# DAU_Kupplung_3phasig_V1_10.net
KiCad netlist of a schematic drawn in EAGLE
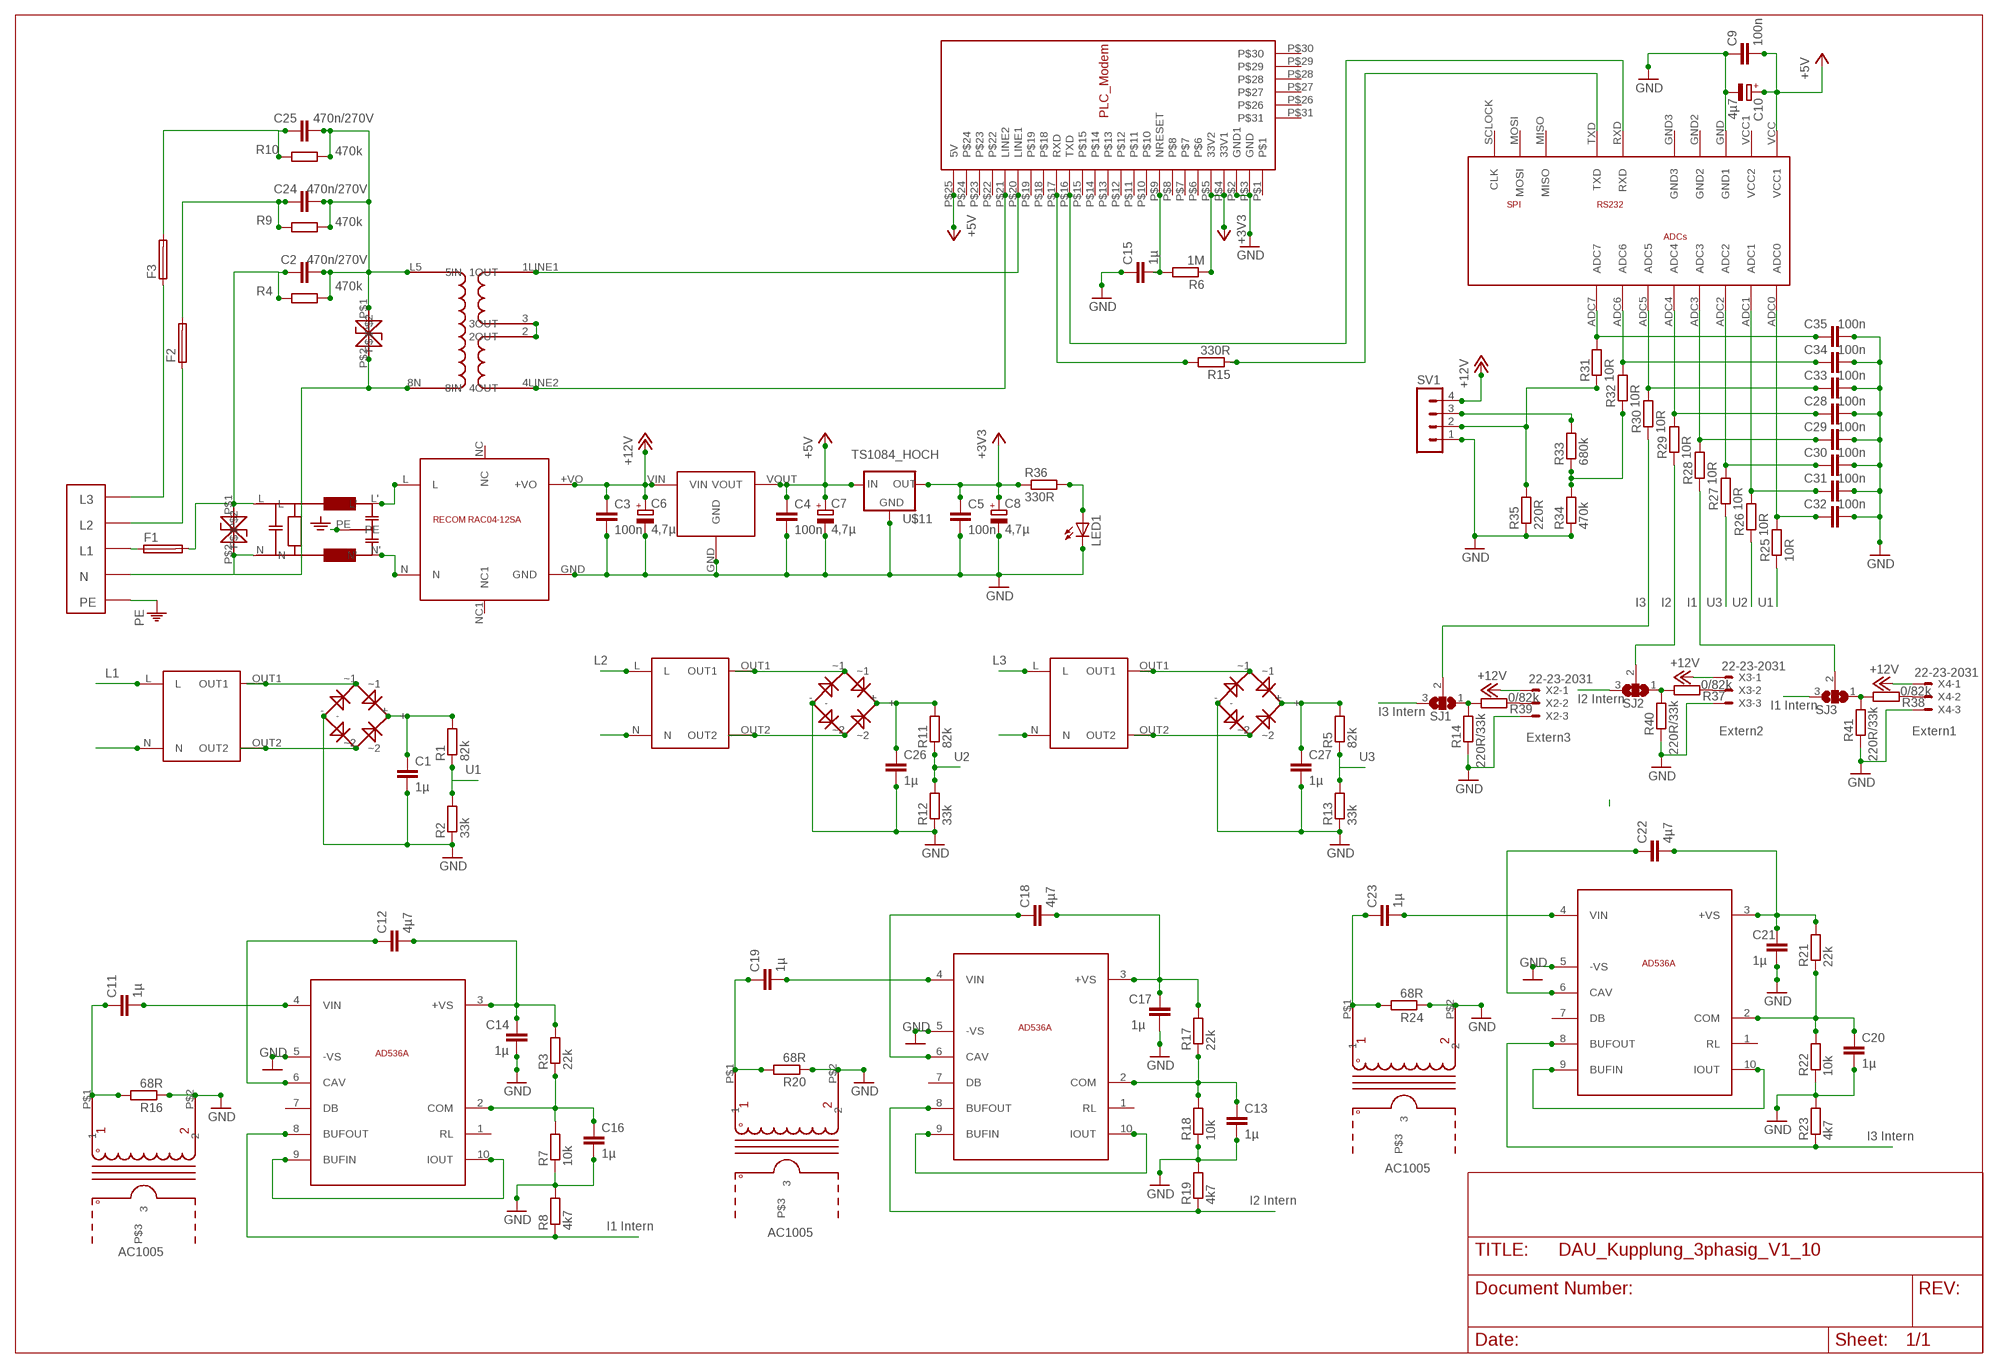
[diagram p0: schematic, sheet 1]

(export (version "E")
  (design (tool "Eeschema 10.0.6"))
  (components
    (comp (ref "AC1002_1")
      (value "AC1010")
      (footprint "eagle-import:AC1010")
      (libsource (lib "eagle-import") (part "AC1010"))
    )
    (comp (ref "C1")
      (value "1µ")
      (footprint "eagle-import:C0805K")
      (libsource (lib "eagle-import") (part "C-EUC0805K"))
    )
    (comp (ref "C2")
      (value "470n/270V")
      (footprint "eagle-import:C225-087X268")
      (libsource (lib "eagle-import") (part "C-EU225-087X268"))
    )
    (comp (ref "C3")
      (value "100n")
      (footprint "eagle-import:C0805K")
      (libsource (lib "eagle-import") (part "C-EUC0805K"))
    )
    (comp (ref "C4")
      (value "100n")
      (footprint "eagle-import:C0805K")
      (libsource (lib "eagle-import") (part "C-EUC0805K"))
    )
    (comp (ref "C5")
      (value "100n")
      (footprint "eagle-import:C0805K")
      (libsource (lib "eagle-import") (part "C-EUC0805K"))
    )
    (comp (ref "C6")
      (value "4,7µ")
      (footprint "eagle-import:E2,5-6")
      (libsource (lib "eagle-import") (part "resistor_CPOL-EUE2.5-6"))
    )
    (comp (ref "C7")
      (value "4,7µ")
      (footprint "eagle-import:E2,5-6")
      (libsource (lib "eagle-import") (part "resistor_CPOL-EUE2.5-6"))
    )
    (comp (ref "C8")
      (value "4,7µ")
      (footprint "eagle-import:E2,5-6")
      (libsource (lib "eagle-import") (part "resistor_CPOL-EUE2.5-6"))
    )
    (comp (ref "C9")
      (value "100n")
      (footprint "eagle-import:C0805K")
      (libsource (lib "eagle-import") (part "C-EUC0805K"))
    )
    (comp (ref "C10")
      (value "4µ7")
      (footprint "eagle-import:E2,5-6E")
      (libsource (lib "eagle-import") (part "CPOL-EUE2,5-6E"))
    )
    (comp (ref "C11")
      (value "1µ")
      (footprint "eagle-import:C0805K")
      (libsource (lib "eagle-import") (part "C-EUC0805K"))
    )
    (comp (ref "C12")
      (value "4µ7")
      (footprint "eagle-import:C0805K")
      (libsource (lib "eagle-import") (part "C-EUC0805K"))
    )
    (comp (ref "C13")
      (value "1µ")
      (footprint "eagle-import:C0805K")
      (libsource (lib "eagle-import") (part "C-EUC0805K"))
    )
    (comp (ref "C14")
      (value "1µ")
      (footprint "eagle-import:C0805K")
      (libsource (lib "eagle-import") (part "C-EUC0805K"))
    )
    (comp (ref "C15")
      (value "1µ")
      (footprint "eagle-import:C0805K")
      (libsource (lib "eagle-import") (part "C-EUC0805K"))
    )
    (comp (ref "C16")
      (value "1µ")
      (footprint "eagle-import:C0805K")
      (libsource (lib "eagle-import") (part "C-EUC0805K"))
    )
    (comp (ref "C17")
      (value "1µ")
      (footprint "eagle-import:C0805K")
      (libsource (lib "eagle-import") (part "C-EUC0805K"))
    )
    (comp (ref "C18")
      (value "4µ7")
      (footprint "eagle-import:C0805K")
      (libsource (lib "eagle-import") (part "C-EUC0805K"))
    )
    (comp (ref "C19")
      (value "1µ")
      (footprint "eagle-import:C0805K")
      (libsource (lib "eagle-import") (part "C-EUC0805K"))
    )
    (comp (ref "C20")
      (value "1µ")
      (footprint "eagle-import:C0805K")
      (libsource (lib "eagle-import") (part "C-EUC0805K"))
    )
    (comp (ref "C21")
      (value "1µ")
      (footprint "eagle-import:C0805K")
      (libsource (lib "eagle-import") (part "C-EUC0805K"))
    )
    (comp (ref "C22")
      (value "4µ7")
      (footprint "eagle-import:C0805K")
      (libsource (lib "eagle-import") (part "C-EUC0805K"))
    )
    (comp (ref "C23")
      (value "1µ")
      (footprint "eagle-import:C0805K")
      (libsource (lib "eagle-import") (part "C-EUC0805K"))
    )
    (comp (ref "C24")
      (value "470n/270V")
      (footprint "eagle-import:C225-087X268")
      (libsource (lib "eagle-import") (part "C-EU225-087X268"))
    )
    (comp (ref "C25")
      (value "470n/270V")
      (footprint "eagle-import:C225-087X268")
      (libsource (lib "eagle-import") (part "C-EU225-087X268"))
    )
    (comp (ref "C26")
      (value "1µ")
      (footprint "eagle-import:C0805K")
      (libsource (lib "eagle-import") (part "C-EUC0805K"))
    )
    (comp (ref "C27")
      (value "1µ")
      (footprint "eagle-import:C0805K")
      (libsource (lib "eagle-import") (part "C-EUC0805K"))
    )
    (comp (ref "C28")
      (value "100n")
      (footprint "eagle-import:C0805K")
      (libsource (lib "eagle-import") (part "C-EUC0805K"))
    )
    (comp (ref "C29")
      (value "100n")
      (footprint "eagle-import:C0805K")
      (libsource (lib "eagle-import") (part "C-EUC0805K"))
    )
    (comp (ref "C30")
      (value "100n")
      (footprint "eagle-import:C0805K")
      (libsource (lib "eagle-import") (part "C-EUC0805K"))
    )
    (comp (ref "C31")
      (value "100n")
      (footprint "eagle-import:C0805K")
      (libsource (lib "eagle-import") (part "C-EUC0805K"))
    )
    (comp (ref "C32")
      (value "100n")
      (footprint "eagle-import:C0805K")
      (libsource (lib "eagle-import") (part "C-EUC0805K"))
    )
    (comp (ref "C33")
      (value "100n")
      (footprint "eagle-import:C0805K")
      (libsource (lib "eagle-import") (part "C-EUC0805K"))
    )
    (comp (ref "C34")
      (value "100n")
      (footprint "eagle-import:C0805K")
      (libsource (lib "eagle-import") (part "C-EUC0805K"))
    )
    (comp (ref "C35")
      (value "100n")
      (footprint "eagle-import:C0805K")
      (libsource (lib "eagle-import") (part "C-EUC0805K"))
    )
    (comp (ref "F1")
      (value "TR5")
      (footprint "eagle-import:TR5")
      (libsource (lib "eagle-import") (part "TR5"))
    )
    (comp (ref "F2")
      (value "TR5")
      (footprint "eagle-import:TR5")
      (fields (field (name "OC_FARNELL") "unknown") (field (name "OC_NEWARK") "unknown"))
      (libsource (lib "eagle-import") (part "TR5"))
    )
    (comp (ref "F3")
      (value "TR5")
      (footprint "eagle-import:TR5")
      (fields (field (name "OC_FARNELL") "unknown") (field (name "OC_NEWARK") "unknown"))
      (libsource (lib "eagle-import") (part "TR5"))
    )
    (comp (ref "LED1")
      (value "LEDSQR2X5")
      (footprint "eagle-import:LED2X5")
      (libsource (lib "eagle-import") (part "LEDSQR2X5"))
    )
    (comp (ref "P6KE300CA")
      (value "P6KE300CA")
      (footprint "eagle-import:TSV")
      (libsource (lib "eagle-import") (part "TSV"))
    )
    (comp (ref "R1")
      (value "82k")
      (footprint "eagle-import:R0805")
      (libsource (lib "eagle-import") (part "R-EU_R0805"))
    )
    (comp (ref "R2")
      (value "33k")
      (footprint "eagle-import:R0805")
      (libsource (lib "eagle-import") (part "R-EU_R0805"))
    )
    (comp (ref "R3")
      (value "22k")
      (footprint "eagle-import:R0805")
      (libsource (lib "eagle-import") (part "R-EU_R0805"))
    )
    (comp (ref "R4")
      (value "470k")
      (footprint "eagle-import:0204_7")
      (libsource (lib "eagle-import") (part "R-EU_0204/7"))
    )
    (comp (ref "R5")
      (value "82k")
      (footprint "eagle-import:R0805")
      (libsource (lib "eagle-import") (part "R-EU_R0805"))
    )
    (comp (ref "R6")
      (value "1M")
      (footprint "eagle-import:R0805")
      (libsource (lib "eagle-import") (part "R-EU_R0805"))
    )
    (comp (ref "R7")
      (value "10k")
      (footprint "eagle-import:R0805")
      (libsource (lib "eagle-import") (part "R-EU_R0805"))
    )
    (comp (ref "R8")
      (value "4k7")
      (footprint "eagle-import:R0805")
      (libsource (lib "eagle-import") (part "R-EU_R0805"))
    )
    (comp (ref "R9")
      (value "470k")
      (footprint "eagle-import:0204_7")
      (libsource (lib "eagle-import") (part "R-EU_0204/7"))
    )
    (comp (ref "R10")
      (value "470k")
      (footprint "eagle-import:0204_7")
      (libsource (lib "eagle-import") (part "R-EU_0204/7"))
    )
    (comp (ref "R11")
      (value "82k")
      (footprint "eagle-import:R0805")
      (libsource (lib "eagle-import") (part "R-EU_R0805"))
    )
    (comp (ref "R12")
      (value "33k")
      (footprint "eagle-import:R0805")
      (libsource (lib "eagle-import") (part "R-EU_R0805"))
    )
    (comp (ref "R13")
      (value "33k")
      (footprint "eagle-import:R0805")
      (libsource (lib "eagle-import") (part "R-EU_R0805"))
    )
    (comp (ref "R14")
      (value "220R/33k")
      (footprint "eagle-import:R0805")
      (libsource (lib "eagle-import") (part "R-EU_R0805"))
    )
    (comp (ref "R15")
      (value "330R")
      (footprint "eagle-import:R0805")
      (libsource (lib "eagle-import") (part "R-EU_R0805"))
    )
    (comp (ref "R16")
      (value "68R")
      (footprint "eagle-import:0204_7")
      (libsource (lib "eagle-import") (part "R-EU_0204/7"))
    )
    (comp (ref "R17")
      (value "22k")
      (footprint "eagle-import:R0805")
      (libsource (lib "eagle-import") (part "R-EU_R0805"))
    )
    (comp (ref "R18")
      (value "10k")
      (footprint "eagle-import:R0805")
      (libsource (lib "eagle-import") (part "R-EU_R0805"))
    )
    (comp (ref "R19")
      (value "4k7")
      (footprint "eagle-import:R0805")
      (libsource (lib "eagle-import") (part "R-EU_R0805"))
    )
    (comp (ref "R20")
      (value "68R")
      (footprint "eagle-import:0204_7")
      (libsource (lib "eagle-import") (part "R-EU_0204/7"))
    )
    (comp (ref "R21")
      (value "22k")
      (footprint "eagle-import:R0805")
      (libsource (lib "eagle-import") (part "R-EU_R0805"))
    )
    (comp (ref "R22")
      (value "10k")
      (footprint "eagle-import:R0805")
      (libsource (lib "eagle-import") (part "R-EU_R0805"))
    )
    (comp (ref "R23")
      (value "4k7")
      (footprint "eagle-import:R0805")
      (libsource (lib "eagle-import") (part "R-EU_R0805"))
    )
    (comp (ref "R24")
      (value "68R")
      (footprint "eagle-import:0204_7")
      (libsource (lib "eagle-import") (part "R-EU_0204/7"))
    )
    (comp (ref "R25")
      (value "10R")
      (footprint "eagle-import:R0805")
      (libsource (lib "eagle-import") (part "R-EU_R0805"))
    )
    (comp (ref "R26")
      (value "10R")
      (footprint "eagle-import:R0805")
      (libsource (lib "eagle-import") (part "R-EU_R0805"))
    )
    (comp (ref "R27")
      (value "10R")
      (footprint "eagle-import:R0805")
      (libsource (lib "eagle-import") (part "R-EU_R0805"))
    )
    (comp (ref "R28")
      (value "10R")
      (footprint "eagle-import:R0805")
      (libsource (lib "eagle-import") (part "R-EU_R0805"))
    )
    (comp (ref "R29")
      (value "10R")
      (footprint "eagle-import:R0805")
      (libsource (lib "eagle-import") (part "R-EU_R0805"))
    )
    (comp (ref "R30")
      (value "10R")
      (footprint "eagle-import:R0805")
      (libsource (lib "eagle-import") (part "R-EU_R0805"))
    )
    (comp (ref "R31")
      (value "10R")
      (footprint "eagle-import:R0805")
      (libsource (lib "eagle-import") (part "R-EU_R0805"))
    )
    (comp (ref "R32")
      (value "10R")
      (footprint "eagle-import:R0805")
      (libsource (lib "eagle-import") (part "R-EU_R0805"))
    )
    (comp (ref "R33")
      (value "680k")
      (footprint "eagle-import:R0805")
      (libsource (lib "eagle-import") (part "R-EU_R0805"))
    )
    (comp (ref "R34")
      (value "470k")
      (footprint "eagle-import:R0805")
      (libsource (lib "eagle-import") (part "R-EU_R0805"))
    )
    (comp (ref "R35")
      (value "220R")
      (footprint "eagle-import:R0805")
      (libsource (lib "eagle-import") (part "R-EU_R0805"))
    )
    (comp (ref "R36")
      (value "330R")
      (footprint "eagle-import:R0805")
      (libsource (lib "eagle-import") (part "R-EU_R0805"))
    )
    (comp (ref "R37")
      (value "0/82k")
      (footprint "eagle-import:R0805")
      (libsource (lib "eagle-import") (part "R-EU_R0805"))
    )
    (comp (ref "R38")
      (value "0/82k")
      (footprint "eagle-import:R0805")
      (libsource (lib "eagle-import") (part "R-EU_R0805"))
    )
    (comp (ref "R39")
      (value "0/82k")
      (footprint "eagle-import:R0805")
      (libsource (lib "eagle-import") (part "R-EU_R0805"))
    )
    (comp (ref "R40")
      (value "220R/33k")
      (footprint "eagle-import:R0805")
      (libsource (lib "eagle-import") (part "R-EU_R0805"))
    )
    (comp (ref "R41")
      (value "220R/33k")
      (footprint "eagle-import:R0805")
      (libsource (lib "eagle-import") (part "R-EU_R0805"))
    )
    (comp (ref "SJ1")
      (value "SJ2WW")
      (footprint "eagle-import:SJ_2W")
      (libsource (lib "eagle-import") (part "SJ2WW"))
    )
    (comp (ref "SJ2")
      (value "SJ2WW")
      (footprint "eagle-import:SJ_2W")
      (libsource (lib "eagle-import") (part "SJ2WW"))
    )
    (comp (ref "SJ3")
      (value "SJ2WW")
      (footprint "eagle-import:SJ_2W")
      (libsource (lib "eagle-import") (part "SJ2WW"))
    )
    (comp (ref "SV1")
      (value "MA04-1")
      (footprint "eagle-import:MA04-1")
      (libsource (lib "eagle-import") (part "MA04-1"))
    )
    (comp (ref "TSV2")
      (value "TSV")
      (footprint "eagle-import:TSV")
      (libsource (lib "eagle-import") (part "TSV"))
    )
    (comp (ref "U$1")
      (value "RECOM_RAC04_12SA")
      (footprint "eagle-import:RAC04_12SA")
      (libsource (lib "eagle-import") (part "RECOM_RAC04_12SA"))
    )
    (comp (ref "U$2")
      (value "SICHERHEITSTRAFO")
      (footprint "eagle-import:TRAFO_0,35VA")
      (libsource (lib "eagle-import") (part "SICHERHEITSTRAFO"))
    )
    (comp (ref "U$3")
      (value "ADUC831_MINIMUM")
      (footprint "eagle-import:ADUC_MINIMUM")
      (libsource (lib "eagle-import") (part "ADUC831_MINIMUM"))
    )
    (comp (ref "U$4")
      (value "MODEMSTECKER")
      (footprint "eagle-import:MODEM_FUSS")
      (libsource (lib "eagle-import") (part "MODEMSTECKER"))
    )
    (comp (ref "U$5")
      (value "PLC_UEBERTRAGER_V2")
      (footprint "eagle-import:PLC-UEBERTRAGER_V2")
      (libsource (lib "eagle-import") (part "PLC_UEBERTRAGER_V2"))
    )
    (comp (ref "U$7")
      (value "AC1010")
      (footprint "eagle-import:AC1010")
      (libsource (lib "eagle-import") (part "AC1010"))
    )
    (comp (ref "U$8")
      (value "RECTIFIER")
      (footprint "eagle-import:RECTIFIER")
      (libsource (lib "eagle-import") (part "RECTIFIER"))
    )
    (comp (ref "U$10")
      (value "RECOM_785_05")
      (footprint "eagle-import:RECOM785X")
      (libsource (lib "eagle-import") (part "RECOM_785_05"))
    )
    (comp (ref "U$11")
      (value "TS1084_HOCH")
      (footprint "eagle-import:TS1084_HOCH")
      (libsource (lib "eagle-import") (part "TS1084_HOCH"))
    )
    (comp (ref "U$12")
      (value "AD536")
      (footprint "eagle-import:TO100_10PIN")
      (libsource (lib "eagle-import") (part "AD536"))
    )
    (comp (ref "U$13")
      (value "AD536")
      (footprint "eagle-import:TO100_10PIN")
      (libsource (lib "eagle-import") (part "AD536"))
    )
    (comp (ref "U$14")
      (value "AC1010")
      (footprint "eagle-import:AC1010")
      (libsource (lib "eagle-import") (part "AC1010"))
    )
    (comp (ref "U$15")
      (value "AD536")
      (footprint "eagle-import:TO100_10PIN")
      (libsource (lib "eagle-import") (part "AD536"))
    )
    (comp (ref "U$16")
      (value "SICHERHEITSTRAFO")
      (footprint "eagle-import:TRAFO_0,35VA")
      (libsource (lib "eagle-import") (part "SICHERHEITSTRAFO"))
    )
    (comp (ref "U$17")
      (value "RECTIFIER")
      (footprint "eagle-import:RECTIFIER")
      (libsource (lib "eagle-import") (part "RECTIFIER"))
    )
    (comp (ref "U$18")
      (value "SICHERHEITSTRAFO")
      (footprint "eagle-import:TRAFO_0,35VA")
      (libsource (lib "eagle-import") (part "SICHERHEITSTRAFO"))
    )
    (comp (ref "U$19")
      (value "RECTIFIER")
      (footprint "eagle-import:RECTIFIER")
      (libsource (lib "eagle-import") (part "RECTIFIER"))
    )
    (comp (ref "U$20")
      (value "NETZFILTER_05_A")
      (footprint "eagle-import:NETZFILTER")
      (libsource (lib "eagle-import") (part "NETZFILTER_05_A"))
    )
    (comp (ref "X1")
      (value "CONNECTO_5_POL")
      (footprint "eagle-import:CONNECTOR_5_POL")
      (libsource (lib "eagle-import") (part "CONNECTO_5_POL"))
    )
    (comp (ref "X2")
      (value "22-23-2031")
      (footprint "eagle-import:22-23-2031")
      (fields (field (name "MF") "MOLEX"))
      (libsource (lib "eagle-import") (part "22-23-2031"))
    )
    (comp (ref "X3")
      (value "22-23-2031")
      (footprint "eagle-import:22-23-2031")
      (fields (field (name "MF") "MOLEX"))
      (libsource (lib "eagle-import") (part "22-23-2031"))
    )
    (comp (ref "X4")
      (value "22-23-2031")
      (footprint "eagle-import:22-23-2031")
      (fields (field (name "MF") "MOLEX"))
      (libsource (lib "eagle-import") (part "22-23-2031"))
    )
  )
  (nets
    (net (code "1") (name "+3V3") (class "Default")
      (node (ref "C5") (pin "1") (pinfunction "1_1") (pintype "passive"))
      (node (ref "C8") (pin "+") (pinfunction "+_+") (pintype "passive"))
      (node (ref "R36") (pin "1") (pinfunction "1_1") (pintype "passive"))
      (node (ref "R6") (pin "1") (pinfunction "1_1") (pintype "passive"))
      (node (ref "U$11") (pin "OUT") (pinfunction "OUT_OUT") (pintype "passive"))
      (node (ref "U$4") (pin "P$4") (pinfunction "33V1_P$4") (pintype "bidirectional"))
      (node (ref "U$4") (pin "P$5") (pinfunction "33V2_P$5") (pintype "bidirectional"))
    )
    (net (code "2") (name "+5V") (class "Default")
      (node (ref "C10") (pin "+") (pinfunction "+_+") (pintype "passive"))
      (node (ref "C4") (pin "1") (pinfunction "1_1") (pintype "passive"))
      (node (ref "C7") (pin "+") (pinfunction "+_+") (pintype "passive"))
      (node (ref "C9") (pin "2") (pinfunction "2_2") (pintype "passive"))
      (node (ref "U$10") (pin "VOUT") (pinfunction "VOUT_VOUT") (pintype "bidirectional"))
      (node (ref "U$11") (pin "IN") (pinfunction "IN_IN") (pintype "input"))
      (node (ref "U$3") (pin "VCC") (pinfunction "VCC1_VCC") (pintype "bidirectional"))
      (node (ref "U$4") (pin "P$25") (pinfunction "5V_P$25") (pintype "bidirectional"))
    )
    (net (code "3") (name "+12V") (class "Default")
      (node (ref "C3") (pin "1") (pinfunction "1_1") (pintype "passive"))
      (node (ref "C6") (pin "+") (pinfunction "+_+") (pintype "passive"))
      (node (ref "SV1") (pin "4") (pinfunction "4_4") (pintype "passive"))
      (node (ref "U$1") (pin "+VO") (pinfunction "+VO_+VO") (pintype "bidirectional"))
      (node (ref "U$10") (pin "VIN") (pinfunction "VIN_VIN") (pintype "bidirectional"))
      (node (ref "X2") (pin "1") (pinfunction "S_1") (pintype "passive"))
      (node (ref "X3") (pin "1") (pinfunction "S_1") (pintype "passive"))
      (node (ref "X4") (pin "1") (pinfunction "S_1") (pintype "passive"))
    )
    (net (code "4") (name "/I1INTERN") (class "Default")
      (node (ref "R8") (pin "1") (pinfunction "1_1") (pintype "passive"))
      (node (ref "SJ3") (pin "3") (pinfunction "3_3") (pintype "passive"))
      (node (ref "U$13") (pin "8") (pinfunction "BUFOUT_8") (pintype "bidirectional"))
    )
    (net (code "5") (name "/I2INTERN") (class "Default")
      (node (ref "R19") (pin "1") (pinfunction "1_1") (pintype "passive"))
      (node (ref "SJ2") (pin "3") (pinfunction "3_3") (pintype "passive"))
      (node (ref "U$12") (pin "8") (pinfunction "BUFOUT_8") (pintype "bidirectional"))
    )
    (net (code "6") (name "/I3INTERN") (class "Default")
      (node (ref "R23") (pin "1") (pinfunction "1_1") (pintype "passive"))
      (node (ref "SJ1") (pin "3") (pinfunction "3_3") (pintype "passive"))
      (node (ref "U$15") (pin "8") (pinfunction "BUFOUT_8") (pintype "bidirectional"))
    )
    (net (code "7") (name "/L1") (class "Default")
      (node (ref "C2") (pin "1") (pinfunction "1_1") (pintype "passive"))
      (node (ref "F1") (pin "2") (pinfunction "2_2") (pintype "passive"))
      (node (ref "P6KE300CA") (pin "P$1") (pinfunction "P$1_P$1") (pintype "bidirectional"))
      (node (ref "R4") (pin "2") (pinfunction "2_2") (pintype "passive"))
      (node (ref "U$2") (pin "L") (pinfunction "L_L") (pintype "bidirectional"))
      (node (ref "U$20") (pin "L") (pinfunction "L_L") (pintype "bidirectional"))
    )
    (net (code "8") (name "/L2") (class "Default")
      (node (ref "C24") (pin "1") (pinfunction "1_1") (pintype "passive"))
      (node (ref "F2") (pin "2") (pinfunction "2_2") (pintype "passive"))
      (node (ref "R9") (pin "2") (pinfunction "2_2") (pintype "passive"))
      (node (ref "U$16") (pin "L") (pinfunction "L_L") (pintype "bidirectional"))
    )
    (net (code "9") (name "/L3") (class "Default")
      (node (ref "C25") (pin "1") (pinfunction "1_1") (pintype "passive"))
      (node (ref "F3") (pin "2") (pinfunction "2_2") (pintype "passive"))
      (node (ref "R10") (pin "2") (pinfunction "2_2") (pintype "passive"))
      (node (ref "U$18") (pin "L") (pinfunction "L_L") (pintype "bidirectional"))
    )
    (net (code "10") (name "/N") (class "Default")
      (node (ref "P6KE300CA") (pin "P$2") (pinfunction "P$2_P$2") (pintype "bidirectional"))
      (node (ref "TSV2") (pin "P$2") (pinfunction "P$2_P$2") (pintype "bidirectional"))
      (node (ref "U$16") (pin "N") (pinfunction "N_N") (pintype "bidirectional"))
      (node (ref "U$18") (pin "N") (pinfunction "N_N") (pintype "bidirectional"))
      (node (ref "U$2") (pin "N") (pinfunction "N_N") (pintype "bidirectional"))
      (node (ref "U$20") (pin "N") (pinfunction "N_N") (pintype "bidirectional"))
      (node (ref "U$5") (pin "8N") (pinfunction "8IN_8N") (pintype "input"))
      (node (ref "X1") (pin "P$4") (pinfunction "P$4_P$4") (pintype "bidirectional"))
    )
    (net (code "11") (name "/U1") (class "Default")
      (node (ref "R1") (pin "1") (pinfunction "1_1") (pintype "passive"))
      (node (ref "R2") (pin "2") (pinfunction "2_2") (pintype "passive"))
      (node (ref "R25") (pin "1") (pinfunction "1_1") (pintype "passive"))
    )
    (net (code "12") (name "/U2") (class "Default")
      (node (ref "R11") (pin "1") (pinfunction "1_1") (pintype "passive"))
      (node (ref "R12") (pin "2") (pinfunction "2_2") (pintype "passive"))
      (node (ref "R26") (pin "1") (pinfunction "1_1") (pintype "passive"))
    )
    (net (code "13") (name "/U3") (class "Default")
      (node (ref "R13") (pin "2") (pinfunction "2_2") (pintype "passive"))
      (node (ref "R27") (pin "1") (pinfunction "1_1") (pintype "passive"))
      (node (ref "R5") (pin "1") (pinfunction "1_1") (pintype "passive"))
    )
    (net (code "14") (name "GND") (class "Default")
      (node (ref "AC1002_1") (pin "P$2") (pinfunction "2_P$2") (pintype "output"))
      (node (ref "C1") (pin "2") (pinfunction "2_2") (pintype "passive"))
      (node (ref "C10") (pin "-") (pinfunction "-_-") (pintype "passive"))
      (node (ref "C13") (pin "2") (pinfunction "2_2") (pintype "passive"))
      (node (ref "C14") (pin "1") (pinfunction "1_1") (pintype "passive"))
      (node (ref "C15") (pin "1") (pinfunction "1_1") (pintype "passive"))
      (node (ref "C16") (pin "2") (pinfunction "2_2") (pintype "passive"))
      (node (ref "C17") (pin "1") (pinfunction "1_1") (pintype "passive"))
      (node (ref "C20") (pin "2") (pinfunction "2_2") (pintype "passive"))
      (node (ref "C21") (pin "2") (pinfunction "2_2") (pintype "passive"))
      (node (ref "C26") (pin "2") (pinfunction "2_2") (pintype "passive"))
      (node (ref "C27") (pin "2") (pinfunction "2_2") (pintype "passive"))
      (node (ref "C28") (pin "2") (pinfunction "2_2") (pintype "passive"))
      (node (ref "C29") (pin "2") (pinfunction "2_2") (pintype "passive"))
      (node (ref "C3") (pin "2") (pinfunction "2_2") (pintype "passive"))
      (node (ref "C30") (pin "2") (pinfunction "2_2") (pintype "passive"))
      (node (ref "C31") (pin "2") (pinfunction "2_2") (pintype "passive"))
      (node (ref "C32") (pin "2") (pinfunction "2_2") (pintype "passive"))
      (node (ref "C33") (pin "2") (pinfunction "2_2") (pintype "passive"))
      (node (ref "C34") (pin "2") (pinfunction "2_2") (pintype "passive"))
      (node (ref "C35") (pin "2") (pinfunction "2_2") (pintype "passive"))
      (node (ref "C4") (pin "2") (pinfunction "2_2") (pintype "passive"))
      (node (ref "C5") (pin "2") (pinfunction "2_2") (pintype "passive"))
      (node (ref "C6") (pin "-") (pinfunction "-_-") (pintype "passive"))
      (node (ref "C7") (pin "-") (pinfunction "-_-") (pintype "passive"))
      (node (ref "C8") (pin "-") (pinfunction "-_-") (pintype "passive"))
      (node (ref "C9") (pin "1") (pinfunction "1_1") (pintype "passive"))
      (node (ref "LED1") (pin "K") (pinfunction "C_K") (pintype "passive"))
      (node (ref "R12") (pin "1") (pinfunction "1_1") (pintype "passive"))
      (node (ref "R13") (pin "1") (pinfunction "1_1") (pintype "passive"))
      (node (ref "R14") (pin "1") (pinfunction "1_1") (pintype "passive"))
      (node (ref "R16") (pin "1") (pinfunction "1_1") (pintype "passive"))
      (node (ref "R18") (pin "1") (pinfunction "1_1") (pintype "passive"))
      (node (ref "R19") (pin "2") (pinfunction "2_2") (pintype "passive"))
      (node (ref "R2") (pin "1") (pinfunction "1_1") (pintype "passive"))
      (node (ref "R20") (pin "1") (pinfunction "1_1") (pintype "passive"))
      (node (ref "R22") (pin "1") (pinfunction "1_1") (pintype "passive"))
      (node (ref "R23") (pin "2") (pinfunction "2_2") (pintype "passive"))
      (node (ref "R24") (pin "1") (pinfunction "1_1") (pintype "passive"))
      (node (ref "R34") (pin "1") (pinfunction "1_1") (pintype "passive"))
      (node (ref "R35") (pin "1") (pinfunction "1_1") (pintype "passive"))
      (node (ref "R40") (pin "1") (pinfunction "1_1") (pintype "passive"))
      (node (ref "R41") (pin "1") (pinfunction "1_1") (pintype "passive"))
      (node (ref "R7") (pin "1") (pinfunction "1_1") (pintype "passive"))
      (node (ref "R8") (pin "2") (pinfunction "2_2") (pintype "passive"))
      (node (ref "SV1") (pin "1") (pinfunction "1_1") (pintype "passive"))
      (node (ref "U$1") (pin "GND") (pinfunction "GND_GND") (pintype "bidirectional"))
      (node (ref "U$10") (pin "GND") (pinfunction "GND_GND") (pintype "bidirectional"))
      (node (ref "U$11") (pin "GND") (pinfunction "GND_GND") (pintype "input"))
      (node (ref "U$12") (pin "5") (pinfunction "-VS_5") (pintype "bidirectional"))
      (node (ref "U$13") (pin "5") (pinfunction "-VS_5") (pintype "bidirectional"))
      (node (ref "U$14") (pin "P$2") (pinfunction "2_P$2") (pintype "output"))
      (node (ref "U$15") (pin "5") (pinfunction "-VS_5") (pintype "bidirectional"))
      (node (ref "U$17") (pin "-") (pinfunction "-_-") (pintype "bidirectional"))
      (node (ref "U$19") (pin "-") (pinfunction "-_-") (pintype "bidirectional"))
      (node (ref "U$3") (pin "GND") (pinfunction "GND1_GND") (pintype "bidirectional"))
      (node (ref "U$4") (pin "P$2") (pinfunction "GND1_P$2") (pintype "bidirectional"))
      (node (ref "U$4") (pin "P$3") (pinfunction "GND_P$3") (pintype "bidirectional"))
      (node (ref "U$7") (pin "P$2") (pinfunction "2_P$2") (pintype "output"))
      (node (ref "U$8") (pin "-") (pinfunction "-_-") (pintype "bidirectional"))
      (node (ref "X2") (pin "3") (pinfunction "S_3") (pintype "passive"))
      (node (ref "X3") (pin "3") (pinfunction "S_3") (pintype "passive"))
      (node (ref "X4") (pin "3") (pinfunction "S_3") (pintype "passive"))
    )
    (net (code "15") (name "Net-(AC1002_1-1)") (class "Default")
      (node (ref "AC1002_1") (pin "P$1") (pinfunction "1_P$1") (pintype "output"))
      (node (ref "C11") (pin "1") (pinfunction "1_1") (pintype "passive"))
      (node (ref "R16") (pin "2") (pinfunction "2_2") (pintype "passive"))
    )
    (net (code "16") (name "Net-(C1-Pad1)") (class "Default")
      (node (ref "C1") (pin "1") (pinfunction "1_1") (pintype "passive"))
      (node (ref "R1") (pin "2") (pinfunction "2_2") (pintype "passive"))
      (node (ref "U$8") (pin "+") (pinfunction "+_+") (pintype "bidirectional"))
    )
    (net (code "17") (name "Net-(C26-Pad1)") (class "Default")
      (node (ref "C26") (pin "1") (pinfunction "1_1") (pintype "passive"))
      (node (ref "R11") (pin "2") (pinfunction "2_2") (pintype "passive"))
      (node (ref "U$17") (pin "+") (pinfunction "+_+") (pintype "bidirectional"))
    )
    (net (code "18") (name "Net-(C27-Pad1)") (class "Default")
      (node (ref "C27") (pin "1") (pinfunction "1_1") (pintype "passive"))
      (node (ref "R5") (pin "2") (pinfunction "2_2") (pintype "passive"))
      (node (ref "U$19") (pin "+") (pinfunction "+_+") (pintype "bidirectional"))
    )
    (net (code "19") (name "Net-(C28-Pad1)") (class "Default")
      (node (ref "C28") (pin "1") (pinfunction "1_1") (pintype "passive"))
      (node (ref "R29") (pin "2") (pinfunction "2_2") (pintype "passive"))
      (node (ref "U$3") (pin "ADC4") (pinfunction "ADC4_ADC4") (pintype "bidirectional"))
    )
    (net (code "20") (name "Net-(C29-Pad1)") (class "Default")
      (node (ref "C29") (pin "1") (pinfunction "1_1") (pintype "passive"))
      (node (ref "R28") (pin "2") (pinfunction "2_2") (pintype "passive"))
      (node (ref "U$3") (pin "ADC3") (pinfunction "ADC3_ADC3") (pintype "bidirectional"))
    )
    (net (code "21") (name "Net-(C30-Pad1)") (class "Default")
      (node (ref "C30") (pin "1") (pinfunction "1_1") (pintype "passive"))
      (node (ref "R27") (pin "2") (pinfunction "2_2") (pintype "passive"))
      (node (ref "U$3") (pin "ADC2") (pinfunction "ADC2_ADC2") (pintype "bidirectional"))
    )
    (net (code "22") (name "Net-(C31-Pad1)") (class "Default")
      (node (ref "C31") (pin "1") (pinfunction "1_1") (pintype "passive"))
      (node (ref "R26") (pin "2") (pinfunction "2_2") (pintype "passive"))
      (node (ref "U$3") (pin "ADC1") (pinfunction "ADC1_ADC1") (pintype "bidirectional"))
    )
    (net (code "23") (name "Net-(C32-Pad1)") (class "Default")
      (node (ref "C32") (pin "1") (pinfunction "1_1") (pintype "passive"))
      (node (ref "R25") (pin "2") (pinfunction "2_2") (pintype "passive"))
      (node (ref "U$3") (pin "ADC0") (pinfunction "ADC0_ADC0") (pintype "bidirectional"))
    )
    (net (code "24") (name "Net-(C33-Pad1)") (class "Default")
      (node (ref "C33") (pin "1") (pinfunction "1_1") (pintype "passive"))
      (node (ref "R30") (pin "2") (pinfunction "2_2") (pintype "passive"))
      (node (ref "U$3") (pin "ADC5") (pinfunction "ADC5_ADC5") (pintype "bidirectional"))
    )
    (net (code "25") (name "Net-(C34-Pad1)") (class "Default")
      (node (ref "C34") (pin "1") (pinfunction "1_1") (pintype "passive"))
      (node (ref "R32") (pin "2") (pinfunction "2_2") (pintype "passive"))
      (node (ref "U$3") (pin "ADC6") (pinfunction "ADC6_ADC6") (pintype "bidirectional"))
    )
    (net (code "26") (name "Net-(C35-Pad1)") (class "Default")
      (node (ref "C35") (pin "1") (pinfunction "1_1") (pintype "passive"))
      (node (ref "R31") (pin "2") (pinfunction "2_2") (pintype "passive"))
      (node (ref "U$3") (pin "ADC7") (pinfunction "ADC7_ADC7") (pintype "bidirectional"))
    )
    (net (code "27") (name "Net-(F1-Pad1)") (class "Default")
      (node (ref "F1") (pin "1") (pinfunction "1_1") (pintype "passive"))
      (node (ref "X1") (pin "P$3") (pinfunction "P$3_P$3") (pintype "bidirectional"))
    )
    (net (code "28") (name "Net-(F2-Pad1)") (class "Default")
      (node (ref "F2") (pin "1") (pinfunction "1_1") (pintype "passive"))
      (node (ref "X1") (pin "P$2") (pinfunction "P$2_P$2") (pintype "bidirectional"))
    )
    (net (code "29") (name "Net-(F3-Pad1)") (class "Default")
      (node (ref "F3") (pin "1") (pinfunction "1_1") (pintype "passive"))
      (node (ref "X1") (pin "P$1") (pinfunction "P$1_P$1") (pintype "bidirectional"))
    )
    (net (code "30") (name "Net-(LED1-PadA)") (class "Default")
      (node (ref "LED1") (pin "A") (pinfunction "A_A") (pintype "passive"))
      (node (ref "R36") (pin "2") (pinfunction "2_2") (pintype "passive"))
    )
    (net (code "31") (name "Net-(R14-Pad2)") (class "Default")
      (node (ref "R14") (pin "2") (pinfunction "2_2") (pintype "passive"))
      (node (ref "R39") (pin "2") (pinfunction "2_2") (pintype "passive"))
      (node (ref "SJ1") (pin "1") (pinfunction "1_1") (pintype "passive"))
    )
    (net (code "32") (name "Net-(R15-Pad1)") (class "Default")
      (node (ref "R15") (pin "1") (pinfunction "1_1") (pintype "passive"))
      (node (ref "U$3") (pin "TXD") (pinfunction "TXD_TXD") (pintype "bidirectional"))
    )
    (net (code "33") (name "Net-(R28-Pad1)") (class "Default")
      (node (ref "R28") (pin "1") (pinfunction "1_1") (pintype "passive"))
      (node (ref "SJ3") (pin "2") (pinfunction "2_2") (pintype "passive"))
    )
    (net (code "34") (name "Net-(R29-Pad1)") (class "Default")
      (node (ref "R29") (pin "1") (pinfunction "1_1") (pintype "passive"))
      (node (ref "SJ2") (pin "2") (pinfunction "2_2") (pintype "passive"))
    )
    (net (code "35") (name "Net-(R30-Pad1)") (class "Default")
      (node (ref "R30") (pin "1") (pinfunction "1_1") (pintype "passive"))
      (node (ref "SJ1") (pin "2") (pinfunction "2_2") (pintype "passive"))
    )
    (net (code "36") (name "Net-(R31-Pad1)") (class "Default")
      (node (ref "R31") (pin "1") (pinfunction "1_1") (pintype "passive"))
      (node (ref "R35") (pin "2") (pinfunction "2_2") (pintype "passive"))
      (node (ref "SV1") (pin "2") (pinfunction "2_2") (pintype "passive"))
    )
    (net (code "37") (name "Net-(R32-Pad1)") (class "Default")
      (node (ref "R32") (pin "1") (pinfunction "1_1") (pintype "passive"))
      (node (ref "R33") (pin "1") (pinfunction "1_1") (pintype "passive"))
      (node (ref "R34") (pin "2") (pinfunction "2_2") (pintype "passive"))
    )
    (net (code "38") (name "Net-(R33-Pad2)") (class "Default")
      (node (ref "R33") (pin "2") (pinfunction "2_2") (pintype "passive"))
      (node (ref "SV1") (pin "3") (pinfunction "3_3") (pintype "passive"))
    )
    (net (code "39") (name "Net-(R37-Pad2)") (class "Default")
      (node (ref "R37") (pin "2") (pinfunction "2_2") (pintype "passive"))
      (node (ref "R40") (pin "2") (pinfunction "2_2") (pintype "passive"))
      (node (ref "SJ2") (pin "1") (pinfunction "1_1") (pintype "passive"))
    )
    (net (code "40") (name "Net-(R38-Pad2)") (class "Default")
      (node (ref "R38") (pin "2") (pinfunction "2_2") (pintype "passive"))
      (node (ref "R41") (pin "2") (pinfunction "2_2") (pintype "passive"))
      (node (ref "SJ3") (pin "1") (pinfunction "1_1") (pintype "passive"))
    )
    (net (code "41") (name "Net-(U$1-PadL)") (class "Default")
      (node (ref "U$1") (pin "L") (pinfunction "L_L") (pintype "bidirectional"))
      (node (ref "U$20") (pin "L'") (pinfunction "L'_L'") (pintype "bidirectional"))
    )
    (net (code "42") (name "Net-(U$1-PadN)") (class "Default")
      (node (ref "U$1") (pin "N") (pinfunction "N_N") (pintype "bidirectional"))
      (node (ref "U$20") (pin "N'") (pinfunction "N'_N'") (pintype "bidirectional"))
    )
    (net (code "43") (name "Net-(U$4-LINE1)") (class "Default")
      (node (ref "U$4") (pin "P$20") (pinfunction "LINE1_P$20") (pintype "bidirectional"))
      (node (ref "U$5") (pin "1LINE1") (pinfunction "1OUT_1LINE1") (pintype "output"))
    )
    (net (code "44") (name "Net-(U$4-LINE2)") (class "Default")
      (node (ref "U$4") (pin "P$21") (pinfunction "LINE2_P$21") (pintype "bidirectional"))
      (node (ref "U$5") (pin "4LINE2") (pinfunction "4OUT_4LINE2") (pintype "output"))
    )
    (net (code "45") (name "Net-(U$4-NRESET)") (class "Default")
      (node (ref "C15") (pin "2") (pinfunction "2_2") (pintype "passive"))
      (node (ref "R6") (pin "2") (pinfunction "2_2") (pintype "passive"))
      (node (ref "U$4") (pin "P$9") (pinfunction "NRESET_P$9") (pintype "bidirectional"))
    )
    (net (code "46") (name "Net-(U$4-RXD)") (class "Default")
      (node (ref "R15") (pin "2") (pinfunction "2_2") (pintype "passive"))
      (node (ref "U$4") (pin "P$17") (pinfunction "RXD_P$17") (pintype "bidirectional"))
    )
    (net (code "47") (name "Net-(U$4-TXD)") (class "Default")
      (node (ref "U$3") (pin "RXD") (pinfunction "RXD_RXD") (pintype "bidirectional"))
      (node (ref "U$4") (pin "P$16") (pinfunction "TXD_P$16") (pintype "bidirectional"))
    )
    (net (code "48") (name "Net-(U$5-2OUT)") (class "Default")
      (node (ref "U$5") (pin "2") (pinfunction "2OUT_2") (pintype "output"))
      (node (ref "U$5") (pin "3") (pinfunction "3OUT_3") (pintype "output"))
    )
    (net (code "49") (name "Net-(U$5-5IN)") (class "Default")
      (node (ref "C2") (pin "2") (pinfunction "2_2") (pintype "passive"))
      (node (ref "C24") (pin "2") (pinfunction "2_2") (pintype "passive"))
      (node (ref "C25") (pin "2") (pinfunction "2_2") (pintype "passive"))
      (node (ref "R10") (pin "1") (pinfunction "1_1") (pintype "passive"))
      (node (ref "R4") (pin "1") (pinfunction "1_1") (pintype "passive"))
      (node (ref "R9") (pin "1") (pinfunction "1_1") (pintype "passive"))
      (node (ref "TSV2") (pin "P$1") (pinfunction "P$1_P$1") (pintype "bidirectional"))
      (node (ref "U$5") (pin "L5") (pinfunction "5IN_L5") (pintype "input"))
    )
    (net (code "50") (name "Net-(U$7-1)") (class "Default")
      (node (ref "C19") (pin "1") (pinfunction "1_1") (pintype "passive"))
      (node (ref "R20") (pin "2") (pinfunction "2_2") (pintype "passive"))
      (node (ref "U$7") (pin "P$1") (pinfunction "1_P$1") (pintype "output"))
    )
    (net (code "51") (name "Net-(U$8-~{1})") (class "Default")
      (node (ref "U$2") (pin "OUT1") (pinfunction "OUT1_OUT1") (pintype "bidirectional"))
      (node (ref "U$8") (pin "~1") (pinfunction "~{1}_~1") (pintype "bidirectional"))
    )
    (net (code "52") (name "Net-(U$8-~{2})") (class "Default")
      (node (ref "U$2") (pin "OUT2") (pinfunction "OUT2_OUT2") (pintype "bidirectional"))
      (node (ref "U$8") (pin "~2") (pinfunction "~{2}_~2") (pintype "bidirectional"))
    )
    (net (code "53") (name "Net-(U$12-+VS)") (class "Default")
      (node (ref "C17") (pin "2") (pinfunction "2_2") (pintype "passive"))
      (node (ref "C18") (pin "2") (pinfunction "2_2") (pintype "passive"))
      (node (ref "R17") (pin "2") (pinfunction "2_2") (pintype "passive"))
      (node (ref "U$12") (pin "3") (pinfunction "+VS_3") (pintype "bidirectional"))
    )
    (net (code "54") (name "Net-(U$12-BUFIN)") (class "Default")
      (node (ref "U$12") (pin "10") (pinfunction "IOUT_10") (pintype "bidirectional"))
      (node (ref "U$12") (pin "9") (pinfunction "BUFIN_9") (pintype "bidirectional"))
    )
    (net (code "55") (name "Net-(U$12-CAV)") (class "Default")
      (node (ref "C18") (pin "1") (pinfunction "1_1") (pintype "passive"))
      (node (ref "U$12") (pin "6") (pinfunction "CAV_6") (pintype "bidirectional"))
    )
    (net (code "56") (name "Net-(U$12-COM)") (class "Default")
      (node (ref "C13") (pin "1") (pinfunction "1_1") (pintype "passive"))
      (node (ref "R17") (pin "1") (pinfunction "1_1") (pintype "passive"))
      (node (ref "R18") (pin "2") (pinfunction "2_2") (pintype "passive"))
      (node (ref "U$12") (pin "2") (pinfunction "COM_2") (pintype "bidirectional"))
    )
    (net (code "57") (name "Net-(U$12-VIN)") (class "Default")
      (node (ref "C19") (pin "2") (pinfunction "2_2") (pintype "passive"))
      (node (ref "U$12") (pin "4") (pinfunction "VIN_4") (pintype "bidirectional"))
    )
    (net (code "58") (name "Net-(U$13-+VS)") (class "Default")
      (node (ref "C12") (pin "2") (pinfunction "2_2") (pintype "passive"))
      (node (ref "C14") (pin "2") (pinfunction "2_2") (pintype "passive"))
      (node (ref "R3") (pin "2") (pinfunction "2_2") (pintype "passive"))
      (node (ref "U$13") (pin "3") (pinfunction "+VS_3") (pintype "bidirectional"))
    )
    (net (code "59") (name "Net-(U$13-BUFIN)") (class "Default")
      (node (ref "U$13") (pin "10") (pinfunction "IOUT_10") (pintype "bidirectional"))
      (node (ref "U$13") (pin "9") (pinfunction "BUFIN_9") (pintype "bidirectional"))
    )
    (net (code "60") (name "Net-(U$13-CAV)") (class "Default")
      (node (ref "C12") (pin "1") (pinfunction "1_1") (pintype "passive"))
      (node (ref "U$13") (pin "6") (pinfunction "CAV_6") (pintype "bidirectional"))
    )
    (net (code "61") (name "Net-(U$13-COM)") (class "Default")
      (node (ref "C16") (pin "1") (pinfunction "1_1") (pintype "passive"))
      (node (ref "R3") (pin "1") (pinfunction "1_1") (pintype "passive"))
      (node (ref "R7") (pin "2") (pinfunction "2_2") (pintype "passive"))
      (node (ref "U$13") (pin "2") (pinfunction "COM_2") (pintype "bidirectional"))
    )
    (net (code "62") (name "Net-(U$13-VIN)") (class "Default")
      (node (ref "C11") (pin "2") (pinfunction "2_2") (pintype "passive"))
      (node (ref "U$13") (pin "4") (pinfunction "VIN_4") (pintype "bidirectional"))
    )
    (net (code "63") (name "Net-(U$14-1)") (class "Default")
      (node (ref "C23") (pin "1") (pinfunction "1_1") (pintype "passive"))
      (node (ref "R24") (pin "2") (pinfunction "2_2") (pintype "passive"))
      (node (ref "U$14") (pin "P$1") (pinfunction "1_P$1") (pintype "output"))
    )
    (net (code "64") (name "Net-(U$15-+VS)") (class "Default")
      (node (ref "C21") (pin "1") (pinfunction "1_1") (pintype "passive"))
      (node (ref "C22") (pin "2") (pinfunction "2_2") (pintype "passive"))
      (node (ref "R21") (pin "2") (pinfunction "2_2") (pintype "passive"))
      (node (ref "U$15") (pin "3") (pinfunction "+VS_3") (pintype "bidirectional"))
    )
    (net (code "65") (name "Net-(U$15-BUFIN)") (class "Default")
      (node (ref "U$15") (pin "10") (pinfunction "IOUT_10") (pintype "bidirectional"))
      (node (ref "U$15") (pin "9") (pinfunction "BUFIN_9") (pintype "bidirectional"))
    )
    (net (code "66") (name "Net-(U$15-CAV)") (class "Default")
      (node (ref "C22") (pin "1") (pinfunction "1_1") (pintype "passive"))
      (node (ref "U$15") (pin "6") (pinfunction "CAV_6") (pintype "bidirectional"))
    )
    (net (code "67") (name "Net-(U$15-COM)") (class "Default")
      (node (ref "C20") (pin "1") (pinfunction "1_1") (pintype "passive"))
      (node (ref "R21") (pin "1") (pinfunction "1_1") (pintype "passive"))
      (node (ref "R22") (pin "2") (pinfunction "2_2") (pintype "passive"))
      (node (ref "U$15") (pin "2") (pinfunction "COM_2") (pintype "bidirectional"))
    )
    (net (code "68") (name "Net-(U$15-VIN)") (class "Default")
      (node (ref "C23") (pin "2") (pinfunction "2_2") (pintype "passive"))
      (node (ref "U$15") (pin "4") (pinfunction "VIN_4") (pintype "bidirectional"))
    )
    (net (code "69") (name "Net-(U$17-~{1})") (class "Default")
      (node (ref "U$16") (pin "OUT1") (pinfunction "OUT1_OUT1") (pintype "bidirectional"))
      (node (ref "U$17") (pin "~1") (pinfunction "~{1}_~1") (pintype "bidirectional"))
    )
    (net (code "70") (name "Net-(U$17-~{2})") (class "Default")
      (node (ref "U$16") (pin "OUT2") (pinfunction "OUT2_OUT2") (pintype "bidirectional"))
      (node (ref "U$17") (pin "~2") (pinfunction "~{2}_~2") (pintype "bidirectional"))
    )
    (net (code "71") (name "Net-(U$19-~{1})") (class "Default")
      (node (ref "U$18") (pin "OUT1") (pinfunction "OUT1_OUT1") (pintype "bidirectional"))
      (node (ref "U$19") (pin "~1") (pinfunction "~{1}_~1") (pintype "bidirectional"))
    )
    (net (code "72") (name "Net-(U$19-~{2})") (class "Default")
      (node (ref "U$18") (pin "OUT2") (pinfunction "OUT2_OUT2") (pintype "bidirectional"))
      (node (ref "U$19") (pin "~2") (pinfunction "~{2}_~2") (pintype "bidirectional"))
    )
    (net (code "73") (name "Net-(X2B-S)") (class "Default")
      (node (ref "R39") (pin "1") (pinfunction "1_1") (pintype "passive"))
      (node (ref "X2") (pin "2") (pinfunction "S_2") (pintype "passive"))
    )
    (net (code "74") (name "Net-(X3B-S)") (class "Default")
      (node (ref "R37") (pin "1") (pinfunction "1_1") (pintype "passive"))
      (node (ref "X3") (pin "2") (pinfunction "S_2") (pintype "passive"))
    )
    (net (code "75") (name "Net-(X4B-S)") (class "Default")
      (node (ref "R38") (pin "1") (pinfunction "1_1") (pintype "passive"))
      (node (ref "X4") (pin "2") (pinfunction "S_2") (pintype "passive"))
    )
    (net (code "76") (name "PE") (class "Default")
      (node (ref "U$20") (pin "PE") (pinfunction "PE_PE") (pintype "input"))
      (node (ref "X1") (pin "P$5") (pinfunction "P$5_P$5") (pintype "bidirectional"))
    )
    (net (code "77") (name "unconnected-(AC1002_1-3-PadP$3)") (class "Default")
      (node (ref "AC1002_1") (pin "P$3") (pinfunction "3_P$3") (pintype "no_connect"))
    )
    (net (code "78") (name "unconnected-(U$1-PadNC)") (class "Default")
      (node (ref "U$1") (pin "NC") (pinfunction "NC_NC") (pintype "bidirectional"))
    )
    (net (code "79") (name "unconnected-(U$1-PadNC1)") (class "Default")
      (node (ref "U$1") (pin "NC1") (pinfunction "NC1_NC1") (pintype "bidirectional"))
    )
    (net (code "80") (name "unconnected-(U$3-CLK-PadSCLOCK)") (class "Default")
      (node (ref "U$3") (pin "SCLOCK") (pinfunction "CLK_SCLOCK") (pintype "bidirectional"))
    )
    (net (code "81") (name "unconnected-(U$3-PadGND2)") (class "Default")
      (node (ref "U$3") (pin "GND2") (pinfunction "GND2_GND2") (pintype "bidirectional"))
    )
    (net (code "82") (name "unconnected-(U$3-PadGND3)") (class "Default")
      (node (ref "U$3") (pin "GND3") (pinfunction "GND3_GND3") (pintype "bidirectional"))
    )
    (net (code "83") (name "unconnected-(U$3-PadMISO)") (class "Default")
      (node (ref "U$3") (pin "MISO") (pinfunction "MISO_MISO") (pintype "bidirectional"))
    )
    (net (code "84") (name "unconnected-(U$3-PadMOSI)") (class "Default")
      (node (ref "U$3") (pin "MOSI") (pinfunction "MOSI_MOSI") (pintype "bidirectional"))
    )
    (net (code "85") (name "unconnected-(U$3-VCC2-PadVCC1)") (class "Default")
      (node (ref "U$3") (pin "VCC1") (pinfunction "VCC2_VCC1") (pintype "bidirectional"))
    )
    (net (code "86") (name "unconnected-(U$4-PadP$1)") (class "Default")
      (node (ref "U$4") (pin "P$1") (pinfunction "P$1_P$1") (pintype "bidirectional"))
    )
    (net (code "87") (name "unconnected-(U$4-PadP$6)") (class "Default")
      (node (ref "U$4") (pin "P$6") (pinfunction "P$6_P$6") (pintype "bidirectional"))
    )
    (net (code "88") (name "unconnected-(U$4-PadP$7)") (class "Default")
      (node (ref "U$4") (pin "P$7") (pinfunction "P$7_P$7") (pintype "bidirectional"))
    )
    (net (code "89") (name "unconnected-(U$4-PadP$8)") (class "Default")
      (node (ref "U$4") (pin "P$8") (pinfunction "P$8_P$8") (pintype "bidirectional"))
    )
    (net (code "90") (name "unconnected-(U$4-PadP$10)") (class "Default")
      (node (ref "U$4") (pin "P$10") (pinfunction "P$10_P$10") (pintype "bidirectional"))
    )
    (net (code "91") (name "unconnected-(U$4-PadP$11)") (class "Default")
      (node (ref "U$4") (pin "P$11") (pinfunction "P$11_P$11") (pintype "bidirectional"))
    )
    (net (code "92") (name "unconnected-(U$4-PadP$12)") (class "Default")
      (node (ref "U$4") (pin "P$12") (pinfunction "P$12_P$12") (pintype "bidirectional"))
    )
    (net (code "93") (name "unconnected-(U$4-PadP$13)") (class "Default")
      (node (ref "U$4") (pin "P$13") (pinfunction "P$13_P$13") (pintype "bidirectional"))
    )
    (net (code "94") (name "unconnected-(U$4-PadP$14)") (class "Default")
      (node (ref "U$4") (pin "P$14") (pinfunction "P$14_P$14") (pintype "bidirectional"))
    )
    (net (code "95") (name "unconnected-(U$4-PadP$15)") (class "Default")
      (node (ref "U$4") (pin "P$15") (pinfunction "P$15_P$15") (pintype "bidirectional"))
    )
    (net (code "96") (name "unconnected-(U$4-PadP$18)") (class "Default")
      (node (ref "U$4") (pin "P$18") (pinfunction "P$18_P$18") (pintype "bidirectional"))
    )
    (net (code "97") (name "unconnected-(U$4-PadP$19)") (class "Default")
      (node (ref "U$4") (pin "P$19") (pinfunction "P$19_P$19") (pintype "bidirectional"))
    )
    (net (code "98") (name "unconnected-(U$4-PadP$22)") (class "Default")
      (node (ref "U$4") (pin "P$22") (pinfunction "P$22_P$22") (pintype "bidirectional"))
    )
    (net (code "99") (name "unconnected-(U$4-PadP$23)") (class "Default")
      (node (ref "U$4") (pin "P$23") (pinfunction "P$23_P$23") (pintype "bidirectional"))
    )
    (net (code "100") (name "unconnected-(U$4-PadP$24)") (class "Default")
      (node (ref "U$4") (pin "P$24") (pinfunction "P$24_P$24") (pintype "bidirectional"))
    )
    (net (code "101") (name "unconnected-(U$4-PadP$26)") (class "Default")
      (node (ref "U$4") (pin "P$26") (pinfunction "P$26_P$26") (pintype "bidirectional"))
    )
    (net (code "102") (name "unconnected-(U$4-PadP$27)") (class "Default")
      (node (ref "U$4") (pin "P$27") (pinfunction "P$27_P$27") (pintype "bidirectional"))
    )
    (net (code "103") (name "unconnected-(U$4-PadP$28)") (class "Default")
      (node (ref "U$4") (pin "P$28") (pinfunction "P$28_P$28") (pintype "bidirectional"))
    )
    (net (code "104") (name "unconnected-(U$4-PadP$29)") (class "Default")
      (node (ref "U$4") (pin "P$29") (pinfunction "P$29_P$29") (pintype "bidirectional"))
    )
    (net (code "105") (name "unconnected-(U$4-PadP$30)") (class "Default")
      (node (ref "U$4") (pin "P$30") (pinfunction "P$30_P$30") (pintype "bidirectional"))
    )
    (net (code "106") (name "unconnected-(U$4-PadP$31)") (class "Default")
      (node (ref "U$4") (pin "P$31") (pinfunction "P$31_P$31") (pintype "bidirectional"))
    )
    (net (code "107") (name "unconnected-(U$7-3-PadP$3)") (class "Default")
      (node (ref "U$7") (pin "P$3") (pinfunction "3_P$3") (pintype "no_connect"))
    )
    (net (code "108") (name "unconnected-(U$12-DB-Pad7)") (class "Default")
      (node (ref "U$12") (pin "7") (pinfunction "DB_7") (pintype "bidirectional"))
    )
    (net (code "109") (name "unconnected-(U$12-RL-Pad1)") (class "Default")
      (node (ref "U$12") (pin "1") (pinfunction "RL_1") (pintype "bidirectional"))
    )
    (net (code "110") (name "unconnected-(U$13-DB-Pad7)") (class "Default")
      (node (ref "U$13") (pin "7") (pinfunction "DB_7") (pintype "bidirectional"))
    )
    (net (code "111") (name "unconnected-(U$13-RL-Pad1)") (class "Default")
      (node (ref "U$13") (pin "1") (pinfunction "RL_1") (pintype "bidirectional"))
    )
    (net (code "112") (name "unconnected-(U$14-3-PadP$3)") (class "Default")
      (node (ref "U$14") (pin "P$3") (pinfunction "3_P$3") (pintype "no_connect"))
    )
    (net (code "113") (name "unconnected-(U$15-DB-Pad7)") (class "Default")
      (node (ref "U$15") (pin "7") (pinfunction "DB_7") (pintype "bidirectional"))
    )
    (net (code "114") (name "unconnected-(U$15-RL-Pad1)") (class "Default")
      (node (ref "U$15") (pin "1") (pinfunction "RL_1") (pintype "bidirectional"))
    )
  )
)
